# Switching_Regulator_LV.net
KiCad netlist of a schematic drawn in Altium Designer
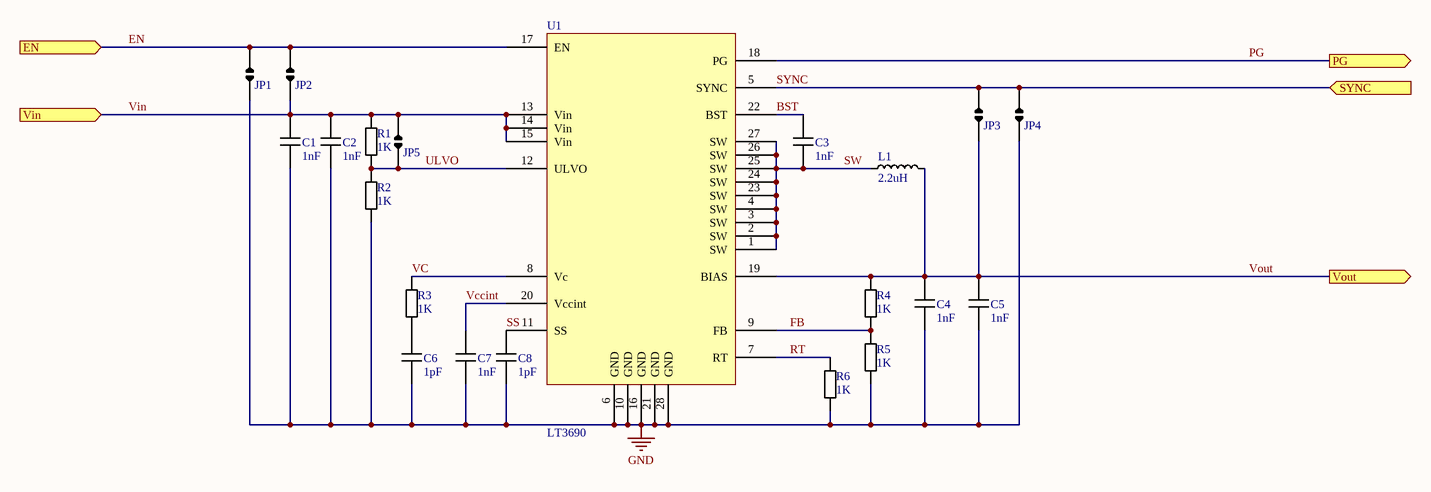
[diagram p0: Switching_Regulator_LV.SchDoc]

(export (version "E")
  (design (tool "Eeschema 10.0.6"))
  (components
    (comp (ref "C1")
      (value "1nF")
      (footprint "0805 Cap")
      (description "0805 MLCC - X7R, 10%")
      (fields (field (name "Comment") "0805 Cap"))
      (libsource (lib "Schlib1") (part "0805 MLCC - X7R, 10%"))
    )
    (comp (ref "C2")
      (value "1nF")
      (footprint "1206 Cap")
      (description "1206 MLCC - X7R, 10%")
      (fields (field (name "Comment") "1206 Cap"))
      (libsource (lib "Schlib1") (part "1206 MLCC - X7R, 10%"))
    )
    (comp (ref "C3")
      (value "1nF")
      (footprint "0805 Cap")
      (description "0805 MLCC - X7R, 10%")
      (fields (field (name "Comment") "0805 Cap"))
      (libsource (lib "Schlib1") (part "0805 MLCC - X7R, 10%"))
    )
    (comp (ref "C4")
      (value "1nF")
      (footprint "0805 Cap")
      (description "0805 MLCC - X7R, 10%")
      (fields (field (name "Comment") "0805 Cap"))
      (libsource (lib "Schlib1") (part "0805 MLCC - X7R, 10%"))
    )
    (comp (ref "C5")
      (value "1nF")
      (footprint "1206 Cap")
      (description "1206 MLCC - X7R, 10%")
      (fields (field (name "Comment") "1206 Cap"))
      (libsource (lib "Schlib1") (part "1206 MLCC - X7R, 10%"))
    )
    (comp (ref "C6")
      (value "1pF")
      (footprint "0805 Cap")
      (description "0805 MLCC - NP0, 5%")
      (fields (field (name "Comment") "0805 Cap"))
      (libsource (lib "Schlib1") (part "0805 MLCC - NP0, 5%"))
    )
    (comp (ref "C7")
      (value "1nF")
      (footprint "0805 Cap")
      (description "0805 MLCC - X7R, 10%")
      (fields (field (name "Comment") "0805 Cap"))
      (libsource (lib "Schlib1") (part "0805 MLCC - X7R, 10%"))
    )
    (comp (ref "C8")
      (value "1pF")
      (footprint "0805 Cap")
      (description "0805 MLCC - NP0, 5%")
      (fields (field (name "Comment") "0805 Cap"))
      (libsource (lib "Schlib1") (part "0805 MLCC - NP0, 5%"))
    )
    (comp (ref "JP1")
      (value "Jumper")
      (footprint "Solder Jumper C")
      (description "Solder Bridge")
      (libsource (lib "Schlib1") (part "Solder Bridge"))
    )
    (comp (ref "JP2")
      (value "Jumper")
      (footprint "Solder Jumper C")
      (description "Solder Bridge")
      (libsource (lib "Schlib1") (part "Solder Bridge"))
    )
    (comp (ref "JP3")
      (value "Jumper")
      (footprint "Solder Jumper C")
      (description "Solder Bridge")
      (libsource (lib "Schlib1") (part "Solder Bridge"))
    )
    (comp (ref "JP4")
      (value "Jumper")
      (footprint "Solder Jumper C")
      (description "Solder Bridge")
      (libsource (lib "Schlib1") (part "Solder Bridge"))
    )
    (comp (ref "JP5")
      (value "Jumper")
      (footprint "Solder Jumper C")
      (description "Solder Bridge")
      (libsource (lib "Schlib1") (part "Solder Bridge"))
    )
    (comp (ref "L1")
      (value "2.2uH")
      (footprint "INDP4037X16N")
      (description "Inductor 4x4mm 2.2uH")
      (fields (field (name "Comment") "LQH44PN2R2MP0"))
      (libsource (lib "Schlib1") (part "LQH44PN2R2MP0"))
    )
    (comp (ref "R1")
      (value "1K")
      (footprint "0805 Resistor")
      (description "0805 Thick Film Resistor 1%")
      (fields (field (name "Comment") "0805 Resistor"))
      (libsource (lib "Schlib1") (part "0805 Thick Film Resistor 1%"))
    )
    (comp (ref "R2")
      (value "1K")
      (footprint "0805 Resistor")
      (description "0805 Thick Film Resistor 1%")
      (fields (field (name "Comment") "0805 Resistor"))
      (libsource (lib "Schlib1") (part "0805 Thick Film Resistor 1%"))
    )
    (comp (ref "R3")
      (value "1K")
      (footprint "0805 Resistor")
      (description "0805 Thick Film Resistor 1%")
      (fields (field (name "Comment") "0805 Resistor"))
      (libsource (lib "Schlib1") (part "0805 Thick Film Resistor 1%"))
    )
    (comp (ref "R4")
      (value "1K")
      (footprint "0805 Resistor")
      (description "0805 Thick Film Resistor 1%")
      (fields (field (name "Comment") "0805 Resistor"))
      (libsource (lib "Schlib1") (part "0805 Thick Film Resistor 1%"))
    )
    (comp (ref "R5")
      (value "1K")
      (footprint "0805 Resistor")
      (description "0805 Thick Film Resistor 1%")
      (fields (field (name "Comment") "0805 Resistor"))
      (libsource (lib "Schlib1") (part "0805 Thick Film Resistor 1%"))
    )
    (comp (ref "R6")
      (value "1K")
      (footprint "0805 Resistor")
      (description "0805 Thick Film Resistor 1%")
      (fields (field (name "Comment") "0805 Resistor"))
      (libsource (lib "Schlib1") (part "0805 Thick Film Resistor 1%"))
    )
    (comp (ref "U1") (value "LT3690") (footprint "LT3690") (libsource (lib "Schlib1") (part "LT3690")))
  )
  (nets
    (net (code "1") (name "/BST") (class "Default")
      (node (ref "C3") (pin "2") (pinfunction "2_2") (pintype "passive"))
      (node (ref "U1") (pin "22") (pinfunction "BST_22") (pintype "passive"))
    )
    (net (code "2") (name "/EN") (class "Default")
      (node (ref "JP1") (pin "1") (pinfunction "1_1") (pintype "passive"))
      (node (ref "JP2") (pin "1") (pinfunction "1_1") (pintype "passive"))
      (node (ref "U1") (pin "17") (pinfunction "EN_17") (pintype "passive"))
    )
    (net (code "3") (name "/FB") (class "Default")
      (node (ref "R4") (pin "1") (pinfunction "1_1") (pintype "passive"))
      (node (ref "R5") (pin "2") (pinfunction "2_2") (pintype "passive"))
      (node (ref "U1") (pin "9") (pinfunction "FB_9") (pintype "passive"))
    )
    (net (code "4") (name "/PG") (class "Default")
      (node (ref "U1") (pin "18") (pinfunction "PG_18") (pintype "passive"))
    )
    (net (code "5") (name "/RT") (class "Default")
      (node (ref "R6") (pin "2") (pinfunction "2_2") (pintype "passive"))
      (node (ref "U1") (pin "7") (pinfunction "RT_7") (pintype "passive"))
    )
    (net (code "6") (name "/SS") (class "Default")
      (node (ref "C8") (pin "2") (pinfunction "2_2") (pintype "passive"))
      (node (ref "U1") (pin "11") (pinfunction "SS_11") (pintype "passive"))
    )
    (net (code "7") (name "/SW") (class "Default")
      (node (ref "C3") (pin "1") (pinfunction "1_1") (pintype "passive"))
      (node (ref "L1") (pin "1") (pinfunction "1_1") (pintype "passive"))
      (node (ref "U1") (pin "1") (pinfunction "SW_1") (pintype "passive"))
      (node (ref "U1") (pin "2") (pinfunction "SW_2") (pintype "passive"))
      (node (ref "U1") (pin "23") (pinfunction "SW_23") (pintype "passive"))
      (node (ref "U1") (pin "24") (pinfunction "SW_24") (pintype "passive"))
      (node (ref "U1") (pin "25") (pinfunction "SW_25") (pintype "passive"))
      (node (ref "U1") (pin "26") (pinfunction "SW_26") (pintype "passive"))
      (node (ref "U1") (pin "27") (pinfunction "SW_27") (pintype "passive"))
      (node (ref "U1") (pin "3") (pinfunction "SW_3") (pintype "passive"))
      (node (ref "U1") (pin "4") (pinfunction "SW_4") (pintype "passive"))
    )
    (net (code "8") (name "/SYNC") (class "Default")
      (node (ref "JP3") (pin "1") (pinfunction "1_1") (pintype "passive"))
      (node (ref "JP4") (pin "1") (pinfunction "1_1") (pintype "passive"))
      (node (ref "U1") (pin "5") (pinfunction "SYNC_5") (pintype "passive"))
    )
    (net (code "9") (name "/ULVO") (class "Default")
      (node (ref "JP5") (pin "2") (pinfunction "2_2") (pintype "passive"))
      (node (ref "R1") (pin "1") (pinfunction "1_1") (pintype "passive"))
      (node (ref "R2") (pin "2") (pinfunction "2_2") (pintype "passive"))
      (node (ref "U1") (pin "12") (pinfunction "ULVO_12") (pintype "passive"))
    )
    (net (code "10") (name "/VC") (class "Default")
      (node (ref "R3") (pin "2") (pinfunction "2_2") (pintype "passive"))
      (node (ref "U1") (pin "8") (pinfunction "Vc_8") (pintype "passive"))
    )
    (net (code "11") (name "/Vccint") (class "Default")
      (node (ref "C7") (pin "2") (pinfunction "2_2") (pintype "passive"))
      (node (ref "U1") (pin "20") (pinfunction "Vccint_20") (pintype "passive"))
    )
    (net (code "12") (name "/Vin") (class "Default")
      (node (ref "C1") (pin "2") (pinfunction "2_2") (pintype "passive"))
      (node (ref "C2") (pin "2") (pinfunction "2_2") (pintype "passive"))
      (node (ref "JP2") (pin "2") (pinfunction "2_2") (pintype "passive"))
      (node (ref "JP5") (pin "1") (pinfunction "1_1") (pintype "passive"))
      (node (ref "R1") (pin "2") (pinfunction "2_2") (pintype "passive"))
      (node (ref "U1") (pin "13") (pinfunction "Vin_13") (pintype "passive"))
      (node (ref "U1") (pin "14") (pinfunction "Vin_14") (pintype "passive"))
      (node (ref "U1") (pin "15") (pinfunction "Vin_15") (pintype "passive"))
    )
    (net (code "13") (name "/Vout") (class "Default")
      (node (ref "C4") (pin "2") (pinfunction "2_2") (pintype "passive"))
      (node (ref "C5") (pin "2") (pinfunction "2_2") (pintype "passive"))
      (node (ref "JP3") (pin "2") (pinfunction "2_2") (pintype "passive"))
      (node (ref "L1") (pin "2") (pinfunction "2_2") (pintype "passive"))
      (node (ref "R4") (pin "2") (pinfunction "2_2") (pintype "passive"))
      (node (ref "U1") (pin "19") (pinfunction "BIAS_19") (pintype "passive"))
    )
    (net (code "14") (name "GND") (class "Default")
      (node (ref "C1") (pin "1") (pinfunction "1_1") (pintype "passive"))
      (node (ref "C2") (pin "1") (pinfunction "1_1") (pintype "passive"))
      (node (ref "C4") (pin "1") (pinfunction "1_1") (pintype "passive"))
      (node (ref "C5") (pin "1") (pinfunction "1_1") (pintype "passive"))
      (node (ref "C6") (pin "1") (pinfunction "1_1") (pintype "passive"))
      (node (ref "C7") (pin "1") (pinfunction "1_1") (pintype "passive"))
      (node (ref "C8") (pin "1") (pinfunction "1_1") (pintype "passive"))
      (node (ref "JP1") (pin "2") (pinfunction "2_2") (pintype "passive"))
      (node (ref "JP4") (pin "2") (pinfunction "2_2") (pintype "passive"))
      (node (ref "R2") (pin "1") (pinfunction "1_1") (pintype "passive"))
      (node (ref "R5") (pin "1") (pinfunction "1_1") (pintype "passive"))
      (node (ref "R6") (pin "1") (pinfunction "1_1") (pintype "passive"))
      (node (ref "U1") (pin "10") (pinfunction "GND_10") (pintype "passive"))
      (node (ref "U1") (pin "16") (pinfunction "GND_16") (pintype "passive"))
      (node (ref "U1") (pin "21") (pinfunction "GND_21") (pintype "passive"))
      (node (ref "U1") (pin "28") (pinfunction "GND_28") (pintype "passive"))
      (node (ref "U1") (pin "6") (pinfunction "GND_6") (pintype "passive"))
    )
    (net (code "15") (name "Net-(C6-Pad2)") (class "Default")
      (node (ref "C6") (pin "2") (pinfunction "2_2") (pintype "passive"))
      (node (ref "R3") (pin "1") (pinfunction "1_1") (pintype "passive"))
    )
  )
)
